# SERVO-Outputs.net
KiCad netlist of a schematic drawn in Altium Designer
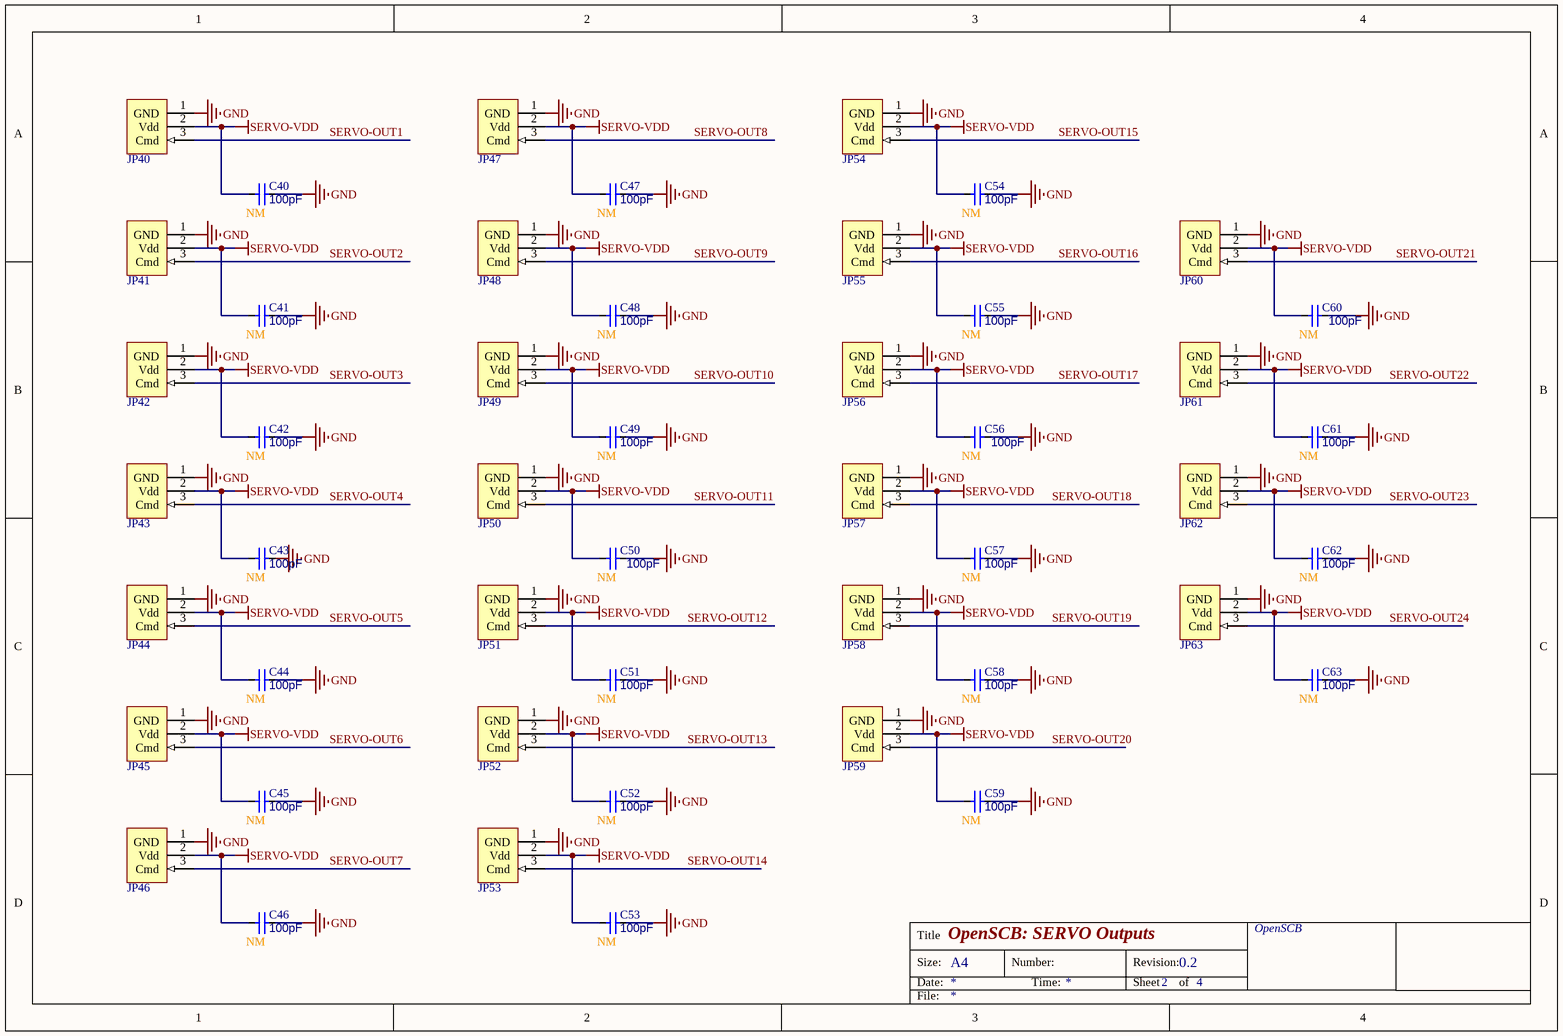
[diagram p0: SERVO-Outputs.SchDoc]

(export (version "E")
  (design (tool "Eeschema 10.0.6"))
  (components
    (comp (ref "C40")
      (value "100pF")
      (footprint "CC1005-0402")
      (fields (field (name "NM") "NM") (field (name "Comment") "Condensateur"))
      (libsource (lib "Common") (part "Condensateur"))
    )
    (comp (ref "C41")
      (value "100pF")
      (footprint "CC1005-0402")
      (fields (field (name "NM") "NM") (field (name "Comment") "Condensateur"))
      (libsource (lib "Common") (part "Condensateur"))
    )
    (comp (ref "C42")
      (value "100pF")
      (footprint "CC1005-0402")
      (fields (field (name "NM") "NM") (field (name "Comment") "Condensateur"))
      (libsource (lib "Common") (part "Condensateur"))
    )
    (comp (ref "C43")
      (value "100pF")
      (footprint "CC1005-0402")
      (fields (field (name "NM") "NM") (field (name "Comment") "Condensateur"))
      (libsource (lib "Common") (part "Condensateur"))
    )
    (comp (ref "C44")
      (value "100pF")
      (footprint "CC1005-0402")
      (fields (field (name "NM") "NM") (field (name "Comment") "Condensateur"))
      (libsource (lib "Common") (part "Condensateur"))
    )
    (comp (ref "C45")
      (value "100pF")
      (footprint "CC1005-0402")
      (fields (field (name "NM") "NM") (field (name "Comment") "Condensateur"))
      (libsource (lib "Common") (part "Condensateur"))
    )
    (comp (ref "C46")
      (value "100pF")
      (footprint "CC1005-0402")
      (fields (field (name "NM") "NM") (field (name "Comment") "Condensateur"))
      (libsource (lib "Common") (part "Condensateur"))
    )
    (comp (ref "C47")
      (value "100pF")
      (footprint "CC1005-0402")
      (fields (field (name "NM") "NM") (field (name "Comment") "Condensateur"))
      (libsource (lib "Common") (part "Condensateur"))
    )
    (comp (ref "C48")
      (value "100pF")
      (footprint "CC1005-0402")
      (fields (field (name "NM") "NM") (field (name "Comment") "Condensateur"))
      (libsource (lib "Common") (part "Condensateur"))
    )
    (comp (ref "C49")
      (value "100pF")
      (footprint "CC1005-0402")
      (fields (field (name "NM") "NM") (field (name "Comment") "Condensateur"))
      (libsource (lib "Common") (part "Condensateur"))
    )
    (comp (ref "C50")
      (value "100pF")
      (footprint "CC1005-0402")
      (fields (field (name "NM") "NM") (field (name "Comment") "Condensateur"))
      (libsource (lib "Common") (part "Condensateur"))
    )
    (comp (ref "C51")
      (value "100pF")
      (footprint "CC1005-0402")
      (fields (field (name "NM") "NM") (field (name "Comment") "Condensateur"))
      (libsource (lib "Common") (part "Condensateur"))
    )
    (comp (ref "C52")
      (value "100pF")
      (footprint "CC1005-0402")
      (fields (field (name "NM") "NM") (field (name "Comment") "Condensateur"))
      (libsource (lib "Common") (part "Condensateur"))
    )
    (comp (ref "C53")
      (value "100pF")
      (footprint "CC1005-0402")
      (fields (field (name "NM") "NM") (field (name "Comment") "Condensateur"))
      (libsource (lib "Common") (part "Condensateur"))
    )
    (comp (ref "C54")
      (value "100pF")
      (footprint "CC1005-0402")
      (fields (field (name "NM") "NM") (field (name "Comment") "Condensateur"))
      (libsource (lib "Common") (part "Condensateur"))
    )
    (comp (ref "C55")
      (value "100pF")
      (footprint "CC1005-0402")
      (fields (field (name "NM") "NM") (field (name "Comment") "Condensateur"))
      (libsource (lib "Common") (part "Condensateur"))
    )
    (comp (ref "C56")
      (value "100pF")
      (footprint "CC1005-0402")
      (fields (field (name "NM") "NM") (field (name "Comment") "Condensateur"))
      (libsource (lib "Common") (part "Condensateur"))
    )
    (comp (ref "C57")
      (value "100pF")
      (footprint "CC1005-0402")
      (fields (field (name "NM") "NM") (field (name "Comment") "Condensateur"))
      (libsource (lib "Common") (part "Condensateur"))
    )
    (comp (ref "C58")
      (value "100pF")
      (footprint "CC1005-0402")
      (fields (field (name "NM") "NM") (field (name "Comment") "Condensateur"))
      (libsource (lib "Common") (part "Condensateur"))
    )
    (comp (ref "C59")
      (value "100pF")
      (footprint "CC1005-0402")
      (fields (field (name "NM") "NM") (field (name "Comment") "Condensateur"))
      (libsource (lib "Common") (part "Condensateur"))
    )
    (comp (ref "C60")
      (value "100pF")
      (footprint "CC1005-0402")
      (fields (field (name "NM") "NM") (field (name "Comment") "Condensateur"))
      (libsource (lib "Common") (part "Condensateur"))
    )
    (comp (ref "C61")
      (value "100pF")
      (footprint "CC1005-0402")
      (fields (field (name "NM") "NM") (field (name "Comment") "Condensateur"))
      (libsource (lib "Common") (part "Condensateur"))
    )
    (comp (ref "C62")
      (value "100pF")
      (footprint "CC1005-0402")
      (fields (field (name "NM") "NM") (field (name "Comment") "Condensateur"))
      (libsource (lib "Common") (part "Condensateur"))
    )
    (comp (ref "C63")
      (value "100pF")
      (footprint "CC1005-0402")
      (fields (field (name "NM") "NM") (field (name "Comment") "Condensateur"))
      (libsource (lib "Common") (part "Condensateur"))
    )
    (comp (ref "JP40")
      (value "SERVO Connector")
      (footprint "PinHead-3pts")
      (libsource (lib "OpenSCB") (part "SERVO-Connector"))
    )
    (comp (ref "JP41")
      (value "SERVO Connector")
      (footprint "PinHead-3pts")
      (libsource (lib "OpenSCB") (part "SERVO-Connector"))
    )
    (comp (ref "JP42")
      (value "SERVO Connector")
      (footprint "PinHead-3pts")
      (libsource (lib "OpenSCB") (part "SERVO-Connector"))
    )
    (comp (ref "JP43")
      (value "SERVO Connector")
      (footprint "PinHead-3pts")
      (libsource (lib "OpenSCB") (part "SERVO-Connector"))
    )
    (comp (ref "JP44")
      (value "SERVO Connector")
      (footprint "PinHead-3pts")
      (libsource (lib "OpenSCB") (part "SERVO-Connector"))
    )
    (comp (ref "JP45")
      (value "SERVO Connector")
      (footprint "PinHead-3pts")
      (libsource (lib "OpenSCB") (part "SERVO-Connector"))
    )
    (comp (ref "JP46")
      (value "SERVO Connector")
      (footprint "PinHead-3pts")
      (libsource (lib "OpenSCB") (part "SERVO-Connector"))
    )
    (comp (ref "JP47")
      (value "SERVO Connector")
      (footprint "PinHead-3pts")
      (libsource (lib "OpenSCB") (part "SERVO-Connector"))
    )
    (comp (ref "JP48")
      (value "SERVO Connector")
      (footprint "PinHead-3pts")
      (libsource (lib "OpenSCB") (part "SERVO-Connector"))
    )
    (comp (ref "JP49")
      (value "SERVO Connector")
      (footprint "PinHead-3pts")
      (libsource (lib "OpenSCB") (part "SERVO-Connector"))
    )
    (comp (ref "JP50")
      (value "SERVO Connector")
      (footprint "PinHead-3pts")
      (libsource (lib "OpenSCB") (part "SERVO-Connector"))
    )
    (comp (ref "JP51")
      (value "SERVO Connector")
      (footprint "PinHead-3pts")
      (libsource (lib "OpenSCB") (part "SERVO-Connector"))
    )
    (comp (ref "JP52")
      (value "SERVO Connector")
      (footprint "PinHead-3pts")
      (libsource (lib "OpenSCB") (part "SERVO-Connector"))
    )
    (comp (ref "JP53")
      (value "SERVO Connector")
      (footprint "PinHead-3pts")
      (libsource (lib "OpenSCB") (part "SERVO-Connector"))
    )
    (comp (ref "JP54")
      (value "SERVO Connector")
      (footprint "PinHead-3pts")
      (libsource (lib "OpenSCB") (part "SERVO-Connector"))
    )
    (comp (ref "JP55")
      (value "SERVO Connector")
      (footprint "PinHead-3pts")
      (libsource (lib "OpenSCB") (part "SERVO-Connector"))
    )
    (comp (ref "JP56")
      (value "SERVO Connector")
      (footprint "PinHead-3pts")
      (libsource (lib "OpenSCB") (part "SERVO-Connector"))
    )
    (comp (ref "JP57")
      (value "SERVO Connector")
      (footprint "PinHead-3pts")
      (libsource (lib "OpenSCB") (part "SERVO-Connector"))
    )
    (comp (ref "JP58")
      (value "SERVO Connector")
      (footprint "PinHead-3pts")
      (libsource (lib "OpenSCB") (part "SERVO-Connector"))
    )
    (comp (ref "JP59")
      (value "SERVO Connector")
      (footprint "PinHead-3pts")
      (libsource (lib "OpenSCB") (part "SERVO-Connector"))
    )
    (comp (ref "JP60")
      (value "SERVO Connector")
      (footprint "PinHead-3pts")
      (libsource (lib "OpenSCB") (part "SERVO-Connector"))
    )
    (comp (ref "JP61")
      (value "SERVO Connector")
      (footprint "PinHead-3pts")
      (libsource (lib "OpenSCB") (part "SERVO-Connector"))
    )
    (comp (ref "JP62")
      (value "SERVO Connector")
      (footprint "PinHead-3pts")
      (libsource (lib "OpenSCB") (part "SERVO-Connector"))
    )
    (comp (ref "JP63")
      (value "SERVO Connector")
      (footprint "PinHead-3pts")
      (libsource (lib "OpenSCB") (part "SERVO-Connector"))
    )
  )
  (nets
    (net (code "1") (name "/SERVO-OUT1") (class "Default")
      (node (ref "JP40") (pin "3") (pinfunction "Cmd_3") (pintype "input"))
    )
    (net (code "2") (name "/SERVO-OUT2") (class "Default")
      (node (ref "JP41") (pin "3") (pinfunction "Cmd_3") (pintype "input"))
    )
    (net (code "3") (name "/SERVO-OUT3") (class "Default")
      (node (ref "JP42") (pin "3") (pinfunction "Cmd_3") (pintype "input"))
    )
    (net (code "4") (name "/SERVO-OUT4") (class "Default")
      (node (ref "JP43") (pin "3") (pinfunction "Cmd_3") (pintype "input"))
    )
    (net (code "5") (name "/SERVO-OUT5") (class "Default")
      (node (ref "JP44") (pin "3") (pinfunction "Cmd_3") (pintype "input"))
    )
    (net (code "6") (name "/SERVO-OUT6") (class "Default")
      (node (ref "JP45") (pin "3") (pinfunction "Cmd_3") (pintype "input"))
    )
    (net (code "7") (name "/SERVO-OUT7") (class "Default")
      (node (ref "JP46") (pin "3") (pinfunction "Cmd_3") (pintype "input"))
    )
    (net (code "8") (name "/SERVO-OUT8") (class "Default")
      (node (ref "JP47") (pin "3") (pinfunction "Cmd_3") (pintype "input"))
    )
    (net (code "9") (name "/SERVO-OUT9") (class "Default")
      (node (ref "JP48") (pin "3") (pinfunction "Cmd_3") (pintype "input"))
    )
    (net (code "10") (name "/SERVO-OUT10") (class "Default")
      (node (ref "JP49") (pin "3") (pinfunction "Cmd_3") (pintype "input"))
    )
    (net (code "11") (name "/SERVO-OUT11") (class "Default")
      (node (ref "JP50") (pin "3") (pinfunction "Cmd_3") (pintype "input"))
    )
    (net (code "12") (name "/SERVO-OUT12") (class "Default")
      (node (ref "JP51") (pin "3") (pinfunction "Cmd_3") (pintype "input"))
    )
    (net (code "13") (name "/SERVO-OUT13") (class "Default")
      (node (ref "JP52") (pin "3") (pinfunction "Cmd_3") (pintype "input"))
    )
    (net (code "14") (name "/SERVO-OUT14") (class "Default")
      (node (ref "JP53") (pin "3") (pinfunction "Cmd_3") (pintype "input"))
    )
    (net (code "15") (name "/SERVO-OUT15") (class "Default")
      (node (ref "JP54") (pin "3") (pinfunction "Cmd_3") (pintype "input"))
    )
    (net (code "16") (name "/SERVO-OUT16") (class "Default")
      (node (ref "JP55") (pin "3") (pinfunction "Cmd_3") (pintype "input"))
    )
    (net (code "17") (name "/SERVO-OUT17") (class "Default")
      (node (ref "JP56") (pin "3") (pinfunction "Cmd_3") (pintype "input"))
    )
    (net (code "18") (name "/SERVO-OUT18") (class "Default")
      (node (ref "JP57") (pin "3") (pinfunction "Cmd_3") (pintype "input"))
    )
    (net (code "19") (name "/SERVO-OUT19") (class "Default")
      (node (ref "JP58") (pin "3") (pinfunction "Cmd_3") (pintype "input"))
    )
    (net (code "20") (name "/SERVO-OUT20") (class "Default")
      (node (ref "JP59") (pin "3") (pinfunction "Cmd_3") (pintype "input"))
    )
    (net (code "21") (name "/SERVO-OUT21") (class "Default")
      (node (ref "JP60") (pin "3") (pinfunction "Cmd_3") (pintype "input"))
    )
    (net (code "22") (name "/SERVO-OUT22") (class "Default")
      (node (ref "JP61") (pin "3") (pinfunction "Cmd_3") (pintype "input"))
    )
    (net (code "23") (name "/SERVO-OUT23") (class "Default")
      (node (ref "JP62") (pin "3") (pinfunction "Cmd_3") (pintype "input"))
    )
    (net (code "24") (name "/SERVO-OUT24") (class "Default")
      (node (ref "JP63") (pin "3") (pinfunction "Cmd_3") (pintype "input"))
    )
    (net (code "25") (name "GND") (class "Default")
      (node (ref "C40") (pin "1") (pinfunction "1_1") (pintype "passive"))
      (node (ref "C41") (pin "1") (pinfunction "1_1") (pintype "passive"))
      (node (ref "C42") (pin "1") (pinfunction "1_1") (pintype "passive"))
      (node (ref "C43") (pin "1") (pinfunction "1_1") (pintype "passive"))
      (node (ref "C44") (pin "1") (pinfunction "1_1") (pintype "passive"))
      (node (ref "C45") (pin "1") (pinfunction "1_1") (pintype "passive"))
      (node (ref "C46") (pin "1") (pinfunction "1_1") (pintype "passive"))
      (node (ref "C47") (pin "1") (pinfunction "1_1") (pintype "passive"))
      (node (ref "C48") (pin "1") (pinfunction "1_1") (pintype "passive"))
      (node (ref "C49") (pin "1") (pinfunction "1_1") (pintype "passive"))
      (node (ref "C50") (pin "1") (pinfunction "1_1") (pintype "passive"))
      (node (ref "C51") (pin "1") (pinfunction "1_1") (pintype "passive"))
      (node (ref "C52") (pin "1") (pinfunction "1_1") (pintype "passive"))
      (node (ref "C53") (pin "1") (pinfunction "1_1") (pintype "passive"))
      (node (ref "C54") (pin "1") (pinfunction "1_1") (pintype "passive"))
      (node (ref "C55") (pin "1") (pinfunction "1_1") (pintype "passive"))
      (node (ref "C56") (pin "1") (pinfunction "1_1") (pintype "passive"))
      (node (ref "C57") (pin "1") (pinfunction "1_1") (pintype "passive"))
      (node (ref "C58") (pin "1") (pinfunction "1_1") (pintype "passive"))
      (node (ref "C59") (pin "1") (pinfunction "1_1") (pintype "passive"))
      (node (ref "C60") (pin "1") (pinfunction "1_1") (pintype "passive"))
      (node (ref "C61") (pin "1") (pinfunction "1_1") (pintype "passive"))
      (node (ref "C62") (pin "1") (pinfunction "1_1") (pintype "passive"))
      (node (ref "C63") (pin "1") (pinfunction "1_1") (pintype "passive"))
      (node (ref "JP40") (pin "1") (pinfunction "GND_1") (pintype "power_in"))
      (node (ref "JP41") (pin "1") (pinfunction "GND_1") (pintype "power_in"))
      (node (ref "JP42") (pin "1") (pinfunction "GND_1") (pintype "power_in"))
      (node (ref "JP43") (pin "1") (pinfunction "GND_1") (pintype "power_in"))
      (node (ref "JP44") (pin "1") (pinfunction "GND_1") (pintype "power_in"))
      (node (ref "JP45") (pin "1") (pinfunction "GND_1") (pintype "power_in"))
      (node (ref "JP46") (pin "1") (pinfunction "GND_1") (pintype "power_in"))
      (node (ref "JP47") (pin "1") (pinfunction "GND_1") (pintype "power_in"))
      (node (ref "JP48") (pin "1") (pinfunction "GND_1") (pintype "power_in"))
      (node (ref "JP49") (pin "1") (pinfunction "GND_1") (pintype "power_in"))
      (node (ref "JP50") (pin "1") (pinfunction "GND_1") (pintype "power_in"))
      (node (ref "JP51") (pin "1") (pinfunction "GND_1") (pintype "power_in"))
      (node (ref "JP52") (pin "1") (pinfunction "GND_1") (pintype "power_in"))
      (node (ref "JP53") (pin "1") (pinfunction "GND_1") (pintype "power_in"))
      (node (ref "JP54") (pin "1") (pinfunction "GND_1") (pintype "power_in"))
      (node (ref "JP55") (pin "1") (pinfunction "GND_1") (pintype "power_in"))
      (node (ref "JP56") (pin "1") (pinfunction "GND_1") (pintype "power_in"))
      (node (ref "JP57") (pin "1") (pinfunction "GND_1") (pintype "power_in"))
      (node (ref "JP58") (pin "1") (pinfunction "GND_1") (pintype "power_in"))
      (node (ref "JP59") (pin "1") (pinfunction "GND_1") (pintype "power_in"))
      (node (ref "JP60") (pin "1") (pinfunction "GND_1") (pintype "power_in"))
      (node (ref "JP61") (pin "1") (pinfunction "GND_1") (pintype "power_in"))
      (node (ref "JP62") (pin "1") (pinfunction "GND_1") (pintype "power_in"))
      (node (ref "JP63") (pin "1") (pinfunction "GND_1") (pintype "power_in"))
    )
    (net (code "26") (name "SERVO-VDD") (class "Default")
      (node (ref "C40") (pin "2") (pinfunction "2_2") (pintype "passive"))
      (node (ref "C41") (pin "2") (pinfunction "2_2") (pintype "passive"))
      (node (ref "C42") (pin "2") (pinfunction "2_2") (pintype "passive"))
      (node (ref "C43") (pin "2") (pinfunction "2_2") (pintype "passive"))
      (node (ref "C44") (pin "2") (pinfunction "2_2") (pintype "passive"))
      (node (ref "C45") (pin "2") (pinfunction "2_2") (pintype "passive"))
      (node (ref "C46") (pin "2") (pinfunction "2_2") (pintype "passive"))
      (node (ref "C47") (pin "2") (pinfunction "2_2") (pintype "passive"))
      (node (ref "C48") (pin "2") (pinfunction "2_2") (pintype "passive"))
      (node (ref "C49") (pin "2") (pinfunction "2_2") (pintype "passive"))
      (node (ref "C50") (pin "2") (pinfunction "2_2") (pintype "passive"))
      (node (ref "C51") (pin "2") (pinfunction "2_2") (pintype "passive"))
      (node (ref "C52") (pin "2") (pinfunction "2_2") (pintype "passive"))
      (node (ref "C53") (pin "2") (pinfunction "2_2") (pintype "passive"))
      (node (ref "C54") (pin "2") (pinfunction "2_2") (pintype "passive"))
      (node (ref "C55") (pin "2") (pinfunction "2_2") (pintype "passive"))
      (node (ref "C56") (pin "2") (pinfunction "2_2") (pintype "passive"))
      (node (ref "C57") (pin "2") (pinfunction "2_2") (pintype "passive"))
      (node (ref "C58") (pin "2") (pinfunction "2_2") (pintype "passive"))
      (node (ref "C59") (pin "2") (pinfunction "2_2") (pintype "passive"))
      (node (ref "C60") (pin "2") (pinfunction "2_2") (pintype "passive"))
      (node (ref "C61") (pin "2") (pinfunction "2_2") (pintype "passive"))
      (node (ref "C62") (pin "2") (pinfunction "2_2") (pintype "passive"))
      (node (ref "C63") (pin "2") (pinfunction "2_2") (pintype "passive"))
      (node (ref "JP40") (pin "2") (pinfunction "Vdd_2") (pintype "power_in"))
      (node (ref "JP41") (pin "2") (pinfunction "Vdd_2") (pintype "power_in"))
      (node (ref "JP42") (pin "2") (pinfunction "Vdd_2") (pintype "power_in"))
      (node (ref "JP43") (pin "2") (pinfunction "Vdd_2") (pintype "power_in"))
      (node (ref "JP44") (pin "2") (pinfunction "Vdd_2") (pintype "power_in"))
      (node (ref "JP45") (pin "2") (pinfunction "Vdd_2") (pintype "power_in"))
      (node (ref "JP46") (pin "2") (pinfunction "Vdd_2") (pintype "power_in"))
      (node (ref "JP47") (pin "2") (pinfunction "Vdd_2") (pintype "power_in"))
      (node (ref "JP48") (pin "2") (pinfunction "Vdd_2") (pintype "power_in"))
      (node (ref "JP49") (pin "2") (pinfunction "Vdd_2") (pintype "power_in"))
      (node (ref "JP50") (pin "2") (pinfunction "Vdd_2") (pintype "power_in"))
      (node (ref "JP51") (pin "2") (pinfunction "Vdd_2") (pintype "power_in"))
      (node (ref "JP52") (pin "2") (pinfunction "Vdd_2") (pintype "power_in"))
      (node (ref "JP53") (pin "2") (pinfunction "Vdd_2") (pintype "power_in"))
      (node (ref "JP54") (pin "2") (pinfunction "Vdd_2") (pintype "power_in"))
      (node (ref "JP55") (pin "2") (pinfunction "Vdd_2") (pintype "power_in"))
      (node (ref "JP56") (pin "2") (pinfunction "Vdd_2") (pintype "power_in"))
      (node (ref "JP57") (pin "2") (pinfunction "Vdd_2") (pintype "power_in"))
      (node (ref "JP58") (pin "2") (pinfunction "Vdd_2") (pintype "power_in"))
      (node (ref "JP59") (pin "2") (pinfunction "Vdd_2") (pintype "power_in"))
      (node (ref "JP60") (pin "2") (pinfunction "Vdd_2") (pintype "power_in"))
      (node (ref "JP61") (pin "2") (pinfunction "Vdd_2") (pintype "power_in"))
      (node (ref "JP62") (pin "2") (pinfunction "Vdd_2") (pintype "power_in"))
      (node (ref "JP63") (pin "2") (pinfunction "Vdd_2") (pintype "power_in"))
    )
  )
)
